# skull_black.net
KiCad netlist of a schematic drawn in EAGLE
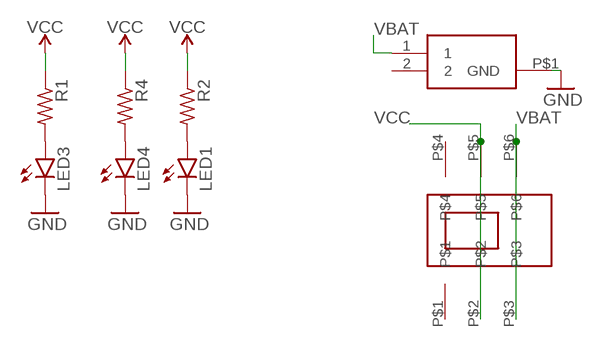
[diagram p0: schematic, sheet 1]

(export (version "E")
  (design (tool "Eeschema 10.0.6"))
  (components
    (comp (ref "LED1")
      (value "LEDCHIP-LED0805")
      (footprint "eagle-import:CHIP-LED0805")
      (libsource (lib "eagle-import") (part "LEDCHIP-LED0805"))
    )
    (comp (ref "LED3")
      (value "LEDCHIP-LED0805")
      (footprint "eagle-import:CHIP-LED0805")
      (libsource (lib "eagle-import") (part "LEDCHIP-LED0805"))
    )
    (comp (ref "LED4")
      (value "LEDCHIP-LED0805")
      (footprint "eagle-import:CHIP-LED0805")
      (libsource (lib "eagle-import") (part "LEDCHIP-LED0805"))
    )
    (comp (ref "R1")
      (value "R-US_R0603")
      (footprint "eagle-import:R0603")
      (libsource (lib "eagle-import") (part "R-US_R0603"))
    )
    (comp (ref "R2")
      (value "R-US_R0603")
      (footprint "eagle-import:R0603")
      (libsource (lib "eagle-import") (part "R-US_R0603"))
    )
    (comp (ref "R4")
      (value "R-US_R0603")
      (footprint "eagle-import:R0603")
      (libsource (lib "eagle-import") (part "R-US_R0603"))
    )
    (comp (ref "U$1")
      (value "CL-SB-22A-02T-SLIDE-SWITCH-TUCKED-PADS")
      (footprint "eagle-import:CL-SB-22A-02T-DPDT-COMPACT-SWITCH")
      (libsource (lib "eagle-import") (part "CL-SB-22A-02T-SLIDE-SWITCH-TUCKED-PADS"))
    )
    (comp (ref "VBAT")
      (value "BAT-HLD-012-SMT")
      (footprint "eagle-import:BATHLD012SMT")
      (fields (field (name "MOUSER_PART_NUMBER") "712-BAT-HLD-012-SMT"))
      (libsource (lib "eagle-import") (part "BAT-HLD-012-SMT"))
    )
  )
  (nets
    (net (code "1") (name "/VBAT") (class "Default")
      (node (ref "U$1") (pin "P$3") (pinfunction "P$3_P$3") (pintype "bidirectional"))
      (node (ref "U$1") (pin "P$6") (pinfunction "P$6_P$6") (pintype "bidirectional"))
      (node (ref "VBAT") (pin "1") (pinfunction "1_1") (pintype "bidirectional"))
    )
    (net (code "2") (name "GND") (class "Default")
      (node (ref "LED1") (pin "C") (pinfunction "C_C") (pintype "passive"))
      (node (ref "LED3") (pin "C") (pinfunction "C_C") (pintype "passive"))
      (node (ref "LED4") (pin "C") (pinfunction "C_C") (pintype "passive"))
      (node (ref "VBAT") (pin "P$1") (pinfunction "GND_P$1") (pintype "bidirectional"))
    )
    (net (code "3") (name "Net-(LED1-PadA)") (class "Default")
      (node (ref "LED1") (pin "A") (pinfunction "A_A") (pintype "passive"))
      (node (ref "R2") (pin "2") (pinfunction "2_2") (pintype "passive"))
    )
    (net (code "4") (name "Net-(LED3-PadA)") (class "Default")
      (node (ref "LED3") (pin "A") (pinfunction "A_A") (pintype "passive"))
      (node (ref "R1") (pin "2") (pinfunction "2_2") (pintype "passive"))
    )
    (net (code "5") (name "Net-(LED4-PadA)") (class "Default")
      (node (ref "LED4") (pin "A") (pinfunction "A_A") (pintype "passive"))
      (node (ref "R4") (pin "2") (pinfunction "2_2") (pintype "passive"))
    )
    (net (code "6") (name "VCC") (class "Default")
      (node (ref "R1") (pin "1") (pinfunction "1_1") (pintype "passive"))
      (node (ref "R2") (pin "1") (pinfunction "1_1") (pintype "passive"))
      (node (ref "R4") (pin "1") (pinfunction "1_1") (pintype "passive"))
      (node (ref "U$1") (pin "P$2") (pinfunction "P$2_P$2") (pintype "bidirectional"))
      (node (ref "U$1") (pin "P$5") (pinfunction "P$5_P$5") (pintype "bidirectional"))
    )
    (net (code "7") (name "unconnected-(U$1-PadP$1)") (class "Default")
      (node (ref "U$1") (pin "P$1") (pinfunction "P$1_P$1") (pintype "bidirectional"))
    )
    (net (code "8") (name "unconnected-(U$1-PadP$4)") (class "Default")
      (node (ref "U$1") (pin "P$4") (pinfunction "P$4_P$4") (pintype "bidirectional"))
    )
    (net (code "9") (name "unconnected-(VBAT-Pad2)") (class "Default")
      (node (ref "VBAT") (pin "2") (pinfunction "2_2") (pintype "bidirectional"))
    )
  )
)
